# 08-3V3_Monitor.net
KiCad netlist of a schematic drawn in Altium Designer
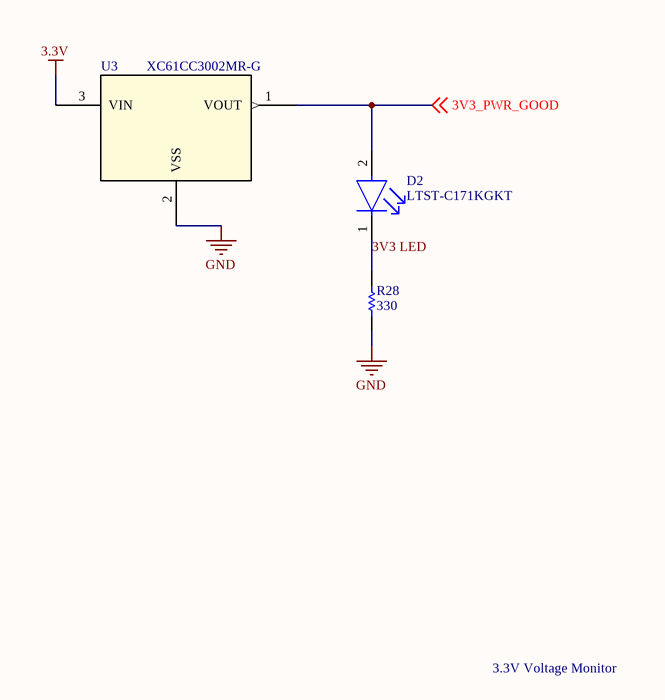
[diagram p0: 08-3V3_Monitor.SchDoc]

(export (version "E")
  (design (tool "Eeschema 10.0.6"))
  (components
    (comp (ref "D2")
      (value "LTST-C171KGKT")
      (footprint "FP-LTST-C171KGKT-MFG")
      (description "LED GREEN CLEAR SMD")
      (libsource (lib "Altium Content Vault") (part "8706943c75ba83719d021d2fdc84c58"))
    )
    (comp (ref "R28")
      (value "330")
      (footprint "RES_0805")
      (description "RES 330 OHM 1% 1/8W 0805")
      (fields (field (name "TOLERANCE") "1%"))
      (libsource (lib "team6") (part "RES_0805_R_330.00"))
    )
    (comp (ref "U3")
      (value "XC61CC3002MR-G")
      (footprint "XC61C_SOT-23_TOR")
      (description "IC SUPERVISOR 1 CHANNEL SOT23")
      (fields (field (name "COPYRIGHT") "Copyright (C) 2022 Ultra Librarian. All rights reserved."))
      (libsource (lib "team6") (part "XC61CC3002MR-G"))
    )
  )
  (nets
    (net (code "1") (name "/3V3 LED") (class "Default")
      (node (ref "D2") (pin "1") (pinfunction "C_1") (pintype "passive"))
      (node (ref "R28") (pin "2") (pinfunction "2_2") (pintype "passive"))
    )
    (net (code "2") (name "3.3V") (class "Default")
      (node (ref "U3") (pin "3") (pinfunction "VIN_3") (pintype "power_in"))
    )
    (net (code "3") (name "3V3_PWR_GOOD") (class "Default")
      (node (ref "D2") (pin "2") (pinfunction "A_2") (pintype "passive"))
      (node (ref "U3") (pin "1") (pinfunction "VOUT_1") (pintype "output"))
    )
    (net (code "4") (name "GND") (class "Default")
      (node (ref "R28") (pin "1") (pinfunction "1_1") (pintype "passive"))
      (node (ref "U3") (pin "2") (pinfunction "VSS_2") (pintype "passive"))
    )
  )
)
